# FMDET.net
KiCad netlist of a schematic drawn in Altium Designer
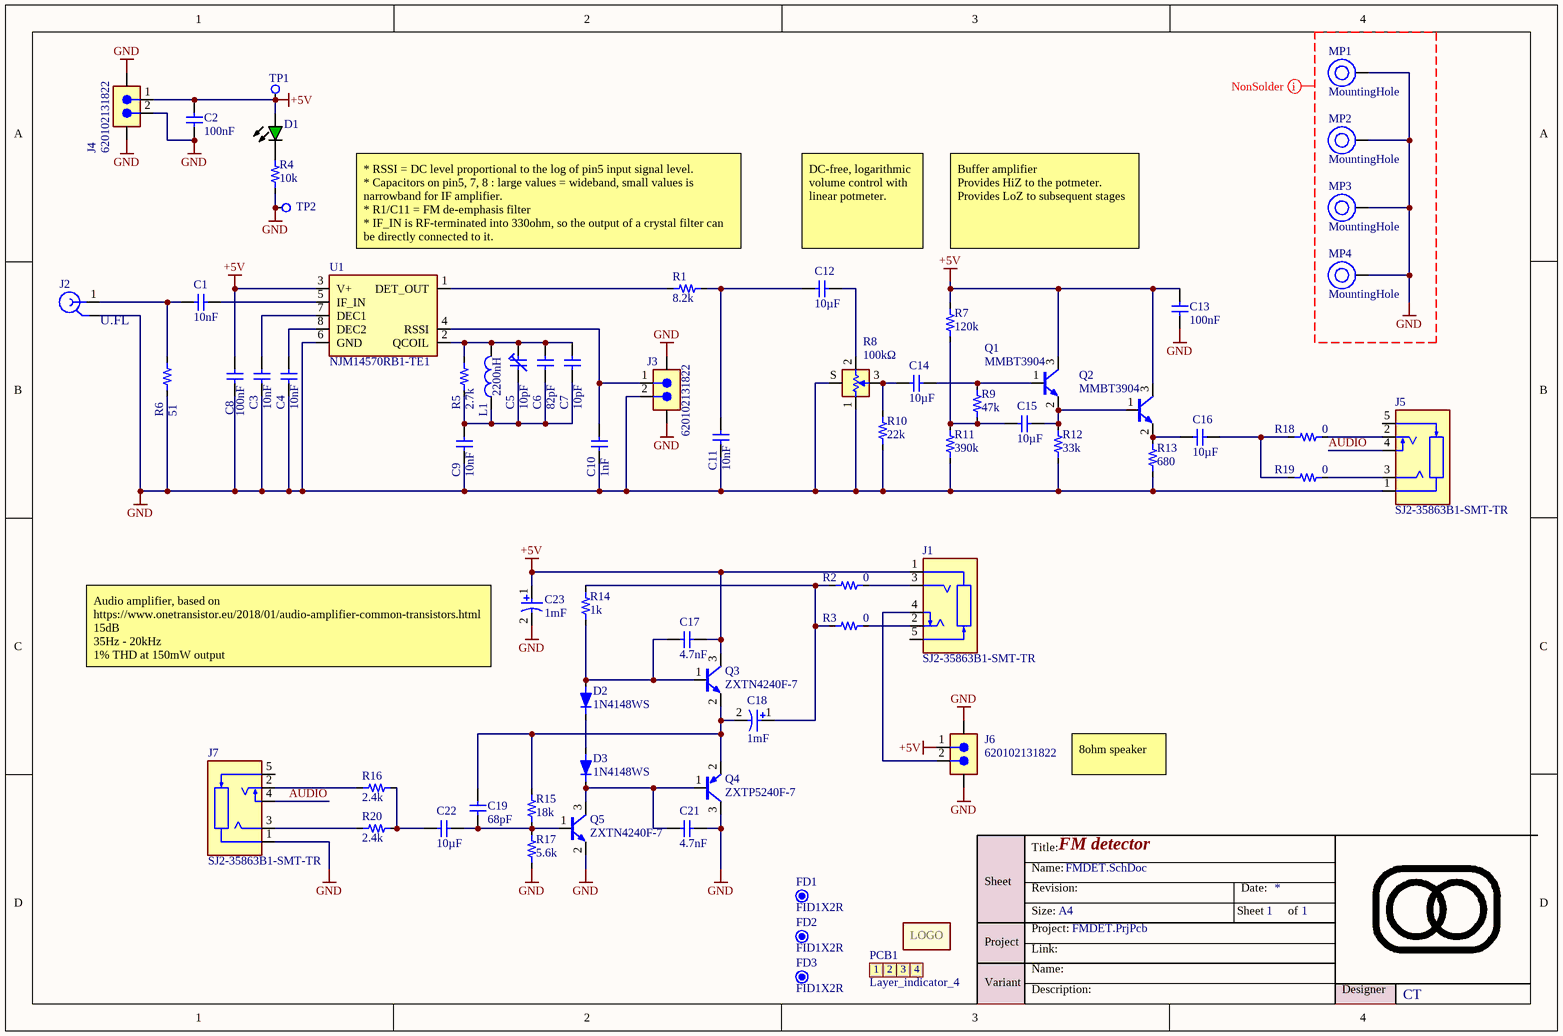
[diagram p0: FMDET.SchDoc]

(export (version "E")
  (design (tool "Eeschema 10.0.6"))
  (components
    (comp (ref "C1")
      (value "10nF")
      (footprint "0603-C-N")
      (description "Capacitor MLCC, General Purpose, size 0603, X7R, 10nF, +/-10%, 50V")
      (fields (field (name "TOLERANCE") "10%") (field (name "JLCPCB PART #") "C57112"))
      (libsource (lib "7c7 Engineering") (part "CAP-NP-2"))
    )
    (comp (ref "C2")
      (value "100nF")
      (footprint "0603-C-N")
      (description "Capacitor MLCC, General Purpose, size 0603, X7R, 100nF, +/-10%, 50V")
      (fields (field (name "TOLERANCE") "10%") (field (name "PAGE PART #") "CCQK104"))
      (libsource (lib "7c7 Engineering") (part "CAP-NP-2"))
    )
    (comp (ref "C3")
      (value "10nF")
      (footprint "0603-C-N")
      (description "Capacitor MLCC, General Purpose, size 0603, X7R, 10nF, +/-10%, 50V")
      (fields (field (name "TOLERANCE") "10%") (field (name "JLCPCB PART #") "C57112"))
      (libsource (lib "7c7 Engineering") (part "CAP-NP-2"))
    )
    (comp (ref "C4")
      (value "10nF")
      (footprint "0603-C-N")
      (description "Capacitor MLCC, General Purpose, size 0603, X7R, 10nF, +/-10%, 50V")
      (fields (field (name "TOLERANCE") "10%") (field (name "JLCPCB PART #") "C57112"))
      (libsource (lib "7c7 Engineering") (part "CAP-NP-2"))
    )
    (comp (ref "C5")
      (value "10pF")
      (footprint "SGC3S100-Footprint-1")
      (fields (field (name "JLCPCB PART #") "C22468121") (field (name "Comment") "SGC3S100"))
      (libsource (lib "7c7 Engineering") (part "CAP-TRIM"))
    )
    (comp (ref "C6")
      (value "82pF")
      (footprint "0603-C-N")
      (description "Multilayer Ceramic Chip Capacitor, General Purpose, size 0603, C0G, 82pF, 50VDC")
      (fields (field (name "TOLERANCE") "5%") (field (name "JLCPCB PART #") "C107056"))
      (libsource (lib "7c7 Engineering") (part "CAP-NP-2"))
    )
    (comp (ref "C7")
      (value "10pF")
      (footprint "0603-C-N")
      (description "WCAP-CSGP Multilayer Ceramic Chip Capacitor, General Purpose, size 0603, NP0, 10pF, 50VDC")
      (fields (field (name "JLCPCB PART #") "C106245") (field (name "TOLERANCE") "5%"))
      (libsource (lib "7c7 Engineering") (part "CAP-NP-2"))
    )
    (comp (ref "C8")
      (value "100nF")
      (footprint "0603-C-N")
      (description "Capacitor MLCC, General Purpose, size 0603, X7R, 100nF, +/-10%, 50V")
      (fields (field (name "TOLERANCE") "10%") (field (name "PAGE PART #") "CCQK104"))
      (libsource (lib "7c7 Engineering") (part "CAP-NP-2"))
    )
    (comp (ref "C9")
      (value "10nF")
      (footprint "0603-C-N")
      (description "Capacitor MLCC, General Purpose, size 0603, X7R, 10nF, +/-10%, 50V")
      (fields (field (name "TOLERANCE") "10%") (field (name "JLCPCB PART #") "C57112"))
      (libsource (lib "7c7 Engineering") (part "CAP-NP-2"))
    )
    (comp (ref "C10")
      (value "1nF")
      (footprint "0603-C-N")
      (description "WCAP-CSGP Multilayer Ceramic Chip Capacitor, General Purpose, size 0603, X7R, 1nF, 50VDC")
      (fields (field (name "TOLERANCE") "10%") (field (name "JLCPCB PART #") "C1588"))
      (libsource (lib "7c7 Engineering") (part "CAP-NP-2"))
    )
    (comp (ref "C11")
      (value "10nF")
      (footprint "0603-C-N")
      (description "Capacitor MLCC, General Purpose, size 0603, X7R, 10nF, +/-10%, 50V")
      (fields (field (name "TOLERANCE") "10%") (field (name "JLCPCB PART #") "C57112"))
      (libsource (lib "7c7 Engineering") (part "CAP-NP-2"))
    )
    (comp (ref "C12")
      (value "10µF")
      (footprint "WCAP-CSGP_1210_L3.2W2.5H2.5")
      (description "WCAP-CSGP Multilayer Ceramic Chip Capacitor, General Purpose, size 1210, X7R, 10µF, 50VDC")
      (fields (field (name "JLCPCB PART #") "C77102") (field (name "TOLERANCE") "10%"))
      (libsource (lib "7c7 Engineering") (part "CAP-NP-2"))
    )
    (comp (ref "C13")
      (value "100nF")
      (footprint "0603-C-N")
      (description "Capacitor MLCC, General Purpose, size 0603, X7R, 100nF, +/-10%, 50V")
      (fields (field (name "TOLERANCE") "10%") (field (name "PAGE PART #") "CCQK104"))
      (libsource (lib "7c7 Engineering") (part "CAP-NP-2"))
    )
    (comp (ref "C14")
      (value "10µF")
      (footprint "WCAP-CSGP_1210_L3.2W2.5H2.5")
      (description "WCAP-CSGP Multilayer Ceramic Chip Capacitor, General Purpose, size 1210, X7R, 10µF, 50VDC")
      (fields (field (name "JLCPCB PART #") "C77102") (field (name "TOLERANCE") "10%"))
      (libsource (lib "7c7 Engineering") (part "CAP-NP-2"))
    )
    (comp (ref "C15")
      (value "10µF")
      (footprint "WCAP-CSGP_1210_L3.2W2.5H2.5")
      (description "WCAP-CSGP Multilayer Ceramic Chip Capacitor, General Purpose, size 1210, X7R, 10µF, 50VDC")
      (fields (field (name "JLCPCB PART #") "C77102") (field (name "TOLERANCE") "10%"))
      (libsource (lib "7c7 Engineering") (part "CAP-NP-2"))
    )
    (comp (ref "C16")
      (value "10µF")
      (footprint "WCAP-CSGP_1210_L3.2W2.5H2.5")
      (description "WCAP-CSGP Multilayer Ceramic Chip Capacitor, General Purpose, size 1210, X7R, 10µF, 50VDC")
      (fields (field (name "JLCPCB PART #") "C77102") (field (name "TOLERANCE") "10%"))
      (libsource (lib "7c7 Engineering") (part "CAP-NP-2"))
    )
    (comp (ref "C17")
      (value "4.7nF")
      (footprint "0603-C-N")
      (description "Capacitor MLCC, General Purpose, size 0603, X7R, 4.7nF, +/-5%, 50V")
      (fields (field (name "TOLERANCE") "5%") (field (name "JLCPCB PART #") "C53987"))
      (libsource (lib "7c7 Engineering") (part "CAP-NP-2"))
    )
    (comp (ref "C18")
      (value "1mF")
      (footprint "WCAP-ATLI_D10H16")
      (description "Alum. Electrolytic Cap 1000F 10V 10MM Radial Wcap-atli; Lifetime 5000H +105°C")
      (fields (field (name "TOLERANCE") "20%") (field (name "JLCPCB PART #") "C43339"))
      (libsource (lib "7c7 Engineering") (part "CAP-P-2"))
    )
    (comp (ref "C19")
      (value "68pF")
      (footprint "0603-C-N")
      (description "Capacitor MLCC, General Purpose, size 0603, C0G, 68pF, +/-5%, 50V")
      (fields (field (name "JLCPCB PART #") "C62782") (field (name "TOLERANCE") "5%"))
      (libsource (lib "7c7 Engineering") (part "CAP-NP-2"))
    )
    (comp (ref "C21")
      (value "4.7nF")
      (footprint "0603-C-N")
      (description "Capacitor MLCC, General Purpose, size 0603, X7R, 4.7nF, +/-5%, 50V")
      (fields (field (name "TOLERANCE") "5%") (field (name "JLCPCB PART #") "C53987"))
      (libsource (lib "7c7 Engineering") (part "CAP-NP-2"))
    )
    (comp (ref "C22")
      (value "10µF")
      (footprint "WCAP-CSGP_1210_L3.2W2.5H2.5")
      (description "WCAP-CSGP Multilayer Ceramic Chip Capacitor, General Purpose, size 1210, X7R, 10µF, 50VDC")
      (fields (field (name "JLCPCB PART #") "C77102") (field (name "TOLERANCE") "10%"))
      (libsource (lib "7c7 Engineering") (part "CAP-NP-2"))
    )
    (comp (ref "C23")
      (value "1mF")
      (footprint "WCAP-ATLI_D10H16")
      (description "Alum. Electrolytic Cap 1000F 10V 10MM Radial Wcap-atli; Lifetime 5000H +105°C")
      (fields (field (name "TOLERANCE") "20%") (field (name "JLCPCB PART #") "C43339"))
      (libsource (lib "7c7 Engineering") (part "CAP-P-2"))
    )
    (comp (ref "D1")
      (value "150060GS84000")
      (footprint "WL-SMCW_0603_150060xx8x000")
      (description "WL-SMCW Mono-color Chip LED Waterclear, size 0603, Green, 3.3V, 40°")
      (fields (field (name "JLCPCB PART #") "C7429914") (field (name "MANUFACTURER") "Wurth Elektronik"))
      (libsource (lib "7c7 Engineering") (part "LED-GREEN-2"))
    )
    (comp (ref "D2")
      (value "1N4148WS")
      (footprint "SOD323-MFG")
      (description "Small Signal Diode, 75 V, 0.15 A, -55 to 150 degC, 2-Pin SOD-323, RoHS, Tape and Reel")
      (fields (field (name "JLCPCB BASIC PART") "Yes") (field (name "JLCPCB PART #") "C2128"))
      (libsource (lib "7c7 Engineering") (part "DIODE-2"))
    )
    (comp (ref "D3")
      (value "1N4148WS")
      (footprint "SOD323-MFG")
      (description "Small Signal Diode, 75 V, 0.15 A, -55 to 150 degC, 2-Pin SOD-323, RoHS, Tape and Reel")
      (fields (field (name "JLCPCB BASIC PART") "Yes") (field (name "JLCPCB PART #") "C2128"))
      (libsource (lib "7c7 Engineering") (part "DIODE-2"))
    )
    (comp (ref "FD1")
      (value "FID1X2R")
      (footprint "FID1X2R")
      (description "Fiducial - Round 1x2mm")
      (libsource (lib "7c7 Engineering") (part "CMP-00134-2"))
    )
    (comp (ref "FD2")
      (value "FID1X2R")
      (footprint "FID1X2R")
      (description "Fiducial - Round 1x2mm")
      (libsource (lib "7c7 Engineering") (part "CMP-00134-2"))
    )
    (comp (ref "FD3")
      (value "FID1X2R")
      (footprint "FID1X2R")
      (description "Fiducial - Round 1x2mm")
      (libsource (lib "7c7 Engineering") (part "CMP-00134-2"))
    )
    (comp (ref "J1")
      (value "SJ2-35863B1-SMT-TR")
      (footprint "SJ2-35863B1-SMT-TR-Footprint-1")
      (description "3.5 mm, Stereo, Right Angle, Surface Mount (SMT), Audio Jack Connector")
      (fields (field (name "JLCPCB PART #") "C381135"))
      (libsource (lib "7c7 Engineering") (part "CN_AUDIO_TRS_2SW"))
    )
    (comp (ref "J2")
      (value "U.FL-R-SMT(10)")
      (footprint "HRS-U.FL-R-SMT_V")
      (fields (field (name "JLCPCB PART #") "C88373") (field (name "MANUFACTURER") "Hirose Electric"))
      (libsource (lib "7c7 Engineering") (part "CN_COAX"))
    )
    (comp (ref "J3")
      (value "620102131822")
      (footprint "620102131822")
      (description "WR-WTB SMT Male Horizontal Shrouded Header, pitch 2mm, 2p")
      (fields
        (field (name "JLCPCB PART #") "C295747")
        (field (name "PAGE PART #") "K620102131822")
        (field (name "PUBLISHER") "Wurth Elektronik")
      )
      (libsource (lib "7c7 Engineering") (part "HDR_2P_2MP"))
    )
    (comp (ref "J4")
      (value "620102131822")
      (footprint "620102131822")
      (description "WR-WTB SMT Male Horizontal Shrouded Header, pitch 2mm, 2p")
      (fields
        (field (name "JLCPCB PART #") "C295747")
        (field (name "PAGE PART #") "K620102131822")
        (field (name "PUBLISHER") "Wurth Elektronik")
      )
      (libsource (lib "") (part "HDR_2P_2MP_1"))
    )
    (comp (ref "J5")
      (value "SJ2-35863B1-SMT-TR")
      (footprint "SJ2-35863B1-SMT-TR-Footprint-1")
      (description "3.5 mm, Stereo, Right Angle, Surface Mount (SMT), Audio Jack Connector")
      (fields (field (name "JLCPCB PART #") "C381135"))
      (libsource (lib "") (part "CN_AUDIO_TRS_2SW_2"))
    )
    (comp (ref "J6")
      (value "620102131822")
      (footprint "620102131822")
      (description "WR-WTB SMT Male Horizontal Shrouded Header, pitch 2mm, 2p")
      (fields
        (field (name "JLCPCB PART #") "C295747")
        (field (name "PAGE PART #") "K620102131822")
        (field (name "PUBLISHER") "Wurth Elektronik")
      )
      (libsource (lib "7c7 Engineering") (part "HDR_2P_2MP"))
    )
    (comp (ref "J7")
      (value "SJ2-35863B1-SMT-TR")
      (footprint "SJ2-35863B1-SMT-TR-Footprint-1")
      (description "3.5 mm, Stereo, Right Angle, Surface Mount (SMT), Audio Jack Connector")
      (fields (field (name "JLCPCB PART #") "C381135"))
      (libsource (lib "") (part "CN_AUDIO_TRS_2SW_1"))
    )
    (comp (ref "L1")
      (value "744762322A")
      (footprint "WE-RFI_1008")
      (description "WE-RFI Ferrite SMT Inductor, size 1008, 2200nH, 200mA, 160MHz")
      (fields
        (field (name "MANUFACTURER") "Wurth Elektronik")
        (field (name "INDUCTANCE") "2200nH")
        (field (name "JLCPCB PART #") "C703712")
      )
      (libsource (lib "7c7 Engineering") (part "IND"))
    )
    (comp (ref "M1")
      (value "Logo")
      (footprint "LOGO_9x6mm")
      (libsource (lib "Integrated_Library_LieBtrau") (part "Logo"))
    )
    (comp (ref "MP1")
      (value "MountingHole")
      (footprint "PTH-M3D6.5_VIA-RING")
      (libsource (lib "7c7 Engineering") (part "MECH_NO_BOM"))
    )
    (comp (ref "MP2")
      (value "MountingHole")
      (footprint "PTH-M3D6.5_VIA-RING")
      (libsource (lib "7c7 Engineering") (part "MECH_NO_BOM"))
    )
    (comp (ref "MP3")
      (value "MountingHole")
      (footprint "PTH-M3D6.5_VIA-RING")
      (libsource (lib "7c7 Engineering") (part "MECH_NO_BOM"))
    )
    (comp (ref "MP4")
      (value "MountingHole")
      (footprint "PTH-M3D6.5_VIA-RING")
      (libsource (lib "7c7 Engineering") (part "MECH_NO_BOM"))
    )
    (comp (ref "PCB1")
      (value "Layer_indicator_4")
      (footprint "LayerId_4L_4x1.5mm")
      (description "Layer indicator for 4 layers")
      (libsource (lib "7c7 Engineering") (part "Layer_indicator_4-Symbol-1"))
    )
    (comp (ref "Q1")
      (value "MMBT3904")
      (footprint "SOT-23-3-N")
      (description "NPN General Purpose Amplifier, 40 V, 0.2 A, -55 to 150 degC, 3-Pin SOT23, RoHS, Tape and Reel")
      (fields (field (name "JLCPCB PART #") "C20526") (field (name "MANUFACTURER") "Fairchild Semiconductor"))
      (libsource (lib "7c7 Engineering") (part "BJT-NPN-BEC"))
    )
    (comp (ref "Q2")
      (value "MMBT3904")
      (footprint "SOT-23-3-N")
      (description "NPN General Purpose Amplifier, 40 V, 0.2 A, -55 to 150 degC, 3-Pin SOT23, RoHS, Tape and Reel")
      (fields (field (name "JLCPCB PART #") "C20526") (field (name "MANUFACTURER") "Fairchild Semiconductor"))
      (libsource (lib "7c7 Engineering") (part "BJT-NPN-BEC"))
    )
    (comp (ref "Q3")
      (value "ZXTN4240F-7")
      (footprint "SOT-23-3-N")
      (description "Trans GP BJT NPN 40V 2A 730mW Automotive 3-Pin SOT-23 T/R")
      (fields (field (name "JLCPCB BASIC PART") "No") (field (name "JLCPCB PART #") "C513079"))
      (libsource (lib "7c7 Engineering") (part "BJT-NPN-BEC"))
    )
    (comp (ref "Q4")
      (value "ZXTP5240F-7")
      (footprint "SOT-23-3-N")
      (description "Bipolar Transistors - BJT 40V PNP SS Mid-Perf Transistor")
      (fields (field (name "JLCPCB BASIC PART") "No") (field (name "JLCPCB PART #") "C3199979"))
      (libsource (lib "7c7 Engineering") (part "BJT-PNP-BEC"))
    )
    (comp (ref "Q5")
      (value "ZXTN4240F-7")
      (footprint "SOT-23-3-N")
      (description "Trans GP BJT NPN 40V 2A 730mW Automotive 3-Pin SOT-23 T/R")
      (fields (field (name "JLCPCB PART #") "C513079") (field (name "JLCPCB BASIC PART") "No"))
      (libsource (lib "7c7 Engineering") (part "BJT-NPN-BEC"))
    )
    (comp (ref "R1")
      (value "8.2k")
      (footprint "0603-R-N")
      (description "Res Thick Film 0603 8.2K Ohm 1% 0.1W(1/10W) ±100ppm/C Pad SMD T/R")
      (fields (field (name "TOLERANCE") "1%") (field (name "JLCPCB PART #") "C25981"))
      (libsource (lib "7c7 Engineering") (part "RES"))
    )
    (comp (ref "R2")
      (value "0")
      (footprint "0603-R-N")
      (description "Chip Jumper, Thick Film, Jumper, 0603, 100mW, 1A, 0 Ohm, <50 mOhm")
      (fields (field (name "FLIR PART #") "YRES0E-1") (field (name "PAGE PART #") "ROQJ0000"))
      (libsource (lib "7c7 Engineering") (part "RES"))
    )
    (comp (ref "R3")
      (value "0")
      (footprint "0603-R-N")
      (description "Chip Jumper, Thick Film, Jumper, 0603, 100mW, 1A, 0 Ohm, <50 mOhm")
      (fields (field (name "FLIR PART #") "YRES0E-1") (field (name "PAGE PART #") "ROQJ0000"))
      (libsource (lib "7c7 Engineering") (part "RES"))
    )
    (comp (ref "R4")
      (value "10k")
      (footprint "0603-R-N")
      (description "Chip Resistor, Thick Film, General Purpose, 0603, 100mW, 50V, 10 kOhm, +/-1%")
      (fields (field (name "FLIR PART #") "YRES10K-1") (field (name "PAGE PART #") "ROQF1002"))
      (libsource (lib "7c7 Engineering") (part "RES"))
    )
    (comp (ref "R5")
      (value "2.7k")
      (footprint "0603-R-N")
      (description "Res Thick Film 0603 2.7K Ohm 1% 0.1W(1/10W) ±100ppm/C Pad SMD Automotive T/R")
      (fields (field (name "TOLERANCE") "1%") (field (name "JLCPCB PART #") "C13167"))
      (libsource (lib "7c7 Engineering") (part "RES"))
    )
    (comp (ref "R6")
      (value "51")
      (footprint "0603-R-N")
      (description "Res Thick Film 0603 51 Ohm 1% 1/10W ±100ppm/°C Molded SMD SMD Paper T/R")
      (fields (field (name "JLCPCB PART #") "C23197") (field (name "TOLERANCE") "1%"))
      (libsource (lib "7c7 Engineering") (part "RES"))
    )
    (comp (ref "R7")
      (value "120k")
      (footprint "0603-R-N")
      (description "Res Thick Film 0603 120K Ohm 1% 0.1W(1/10W) ±100ppm/°C Pad SMD T/R")
      (fields (field (name "TOLERANCE") "1%") (field (name "JLCPCB PART #") "C25808"))
      (libsource (lib "7c7 Engineering") (part "RES"))
    )
    (comp (ref "R8")
      (value "100kΩ")
      (footprint "PTV09A-4020F-B104-Footprint-1")
      (description "Potentiometer, Carbon, 0.05W, 100000ohm, 20V, 20% +/-Tol, 1 Turn(s)")
      (fields (field (name "JLCPCB PART #") "C5154557") (field (name "TOLERANCE") "20%"))
      (libsource (lib "7c7 Engineering") (part "RES-ADJ-3_SHIELD"))
    )
    (comp (ref "R9")
      (value "47k")
      (footprint "0603-R-N")
      (description "Chip Resistor, Thick Film, General Purpose, 0603, 100mW, 50V, 47 kOhm, +/-1%")
      (fields (field (name "FLIR PART #") "YRES47K-1") (field (name "PAGE PART #") "ROQF4702"))
      (libsource (lib "7c7 Engineering") (part "RES"))
    )
    (comp (ref "R10")
      (value "22k")
      (footprint "0603-R-N")
      (description "Chip Resistor, Thick Film, General Purpose, 0603, 100mW, 50V, 22 kOhm, +/-1%")
      (fields (field (name "JLCPCB PART #") "C31850") (field (name "TOLERANCE") "1%"))
      (libsource (lib "7c7 Engineering") (part "RES"))
    )
    (comp (ref "R11")
      (value "390k")
      (footprint "0603-R-N")
      (description "SMD Chip Resistor, 390 kOhm, ± 1%, 100 mW, 0603 [1608 Metric], Thick Film, General Purpose")
      (fields (field (name "JLCPCB PART #") "C23150") (field (name "TOLERANCE") "1%"))
      (libsource (lib "7c7 Engineering") (part "RES"))
    )
    (comp (ref "R12")
      (value "33k")
      (footprint "0603-R-N")
      (description "Chip Resistor, Thick Film, General Purpose, 0603, 100mW, 50V, 33 kOhm, +/-1%")
      (fields (field (name "TOLERANCE") "1%") (field (name "JLCPCB PART #") "C4216"))
      (libsource (lib "7c7 Engineering") (part "RES"))
    )
    (comp (ref "R13")
      (value "680")
      (footprint "0603-R-N")
      (description "SMD Chip Resistor, 680 Ohm, ï¿½ 1%, 100 mW, 0603 [1608 Metric], Thick Film, Precision")
      (fields (field (name "JLCPCB PART #") "C23228") (field (name "TOLERANCE") "1%"))
      (libsource (lib "7c7 Engineering") (part "RES"))
    )
    (comp (ref "R14")
      (value "1k")
      (footprint "0603-R-N")
      (description "Chip Resistor, Thick Film, General Purpose, 0603, 100mW, 50V, 1 kOhm, +/-1%")
      (fields (field (name "JLCPCB BASIC PART") "Yes") (field (name "TOLERANCE") "1%"))
      (libsource (lib "7c7 Engineering") (part "RES"))
    )
    (comp (ref "R15")
      (value "18k")
      (footprint "0603-R-N")
      (description "Chip Resistor, Thick Film, General Purpose, 0603, 100mW, 50V, 18 kOhm, +/-1%")
      (fields (field (name "TOLERANCE") "1%") (field (name "PAGE PART #") "ROQF1802"))
      (libsource (lib "7c7 Engineering") (part "RES"))
    )
    (comp (ref "R16")
      (value "2.4k")
      (footprint "0603-R-N")
      (description "Chip Resistor, Thick Film, General Purpose, 0603, 100mW, 50V, 2.4 kOhm, +/-1%")
      (fields (field (name "JLCPCB PART #") "C22940") (field (name "TOLERANCE") "1%"))
      (libsource (lib "7c7 Engineering") (part "RES"))
    )
    (comp (ref "R17")
      (value "5.6k")
      (footprint "0603-R-N")
      (description "Res Thick Film 0603 5.6K Ohm 1% 0.1W(1/10W) ±100ppm/C Pad SMD T/R")
      (fields (field (name "TOLERANCE") "1%") (field (name "JLCPCB PART #") "C23189"))
      (libsource (lib "7c7 Engineering") (part "RES"))
    )
    (comp (ref "R18")
      (value "0")
      (footprint "0603-R-N")
      (description "Chip Jumper, Thick Film, Jumper, 0603, 100mW, 1A, 0 Ohm, <50 mOhm")
      (fields (field (name "FLIR PART #") "YRES0E-1") (field (name "PAGE PART #") "ROQJ0000"))
      (libsource (lib "7c7 Engineering") (part "RES"))
    )
    (comp (ref "R19")
      (value "0")
      (footprint "0603-R-N")
      (description "Chip Jumper, Thick Film, Jumper, 0603, 100mW, 1A, 0 Ohm, <50 mOhm")
      (fields (field (name "FLIR PART #") "YRES0E-1") (field (name "PAGE PART #") "ROQJ0000"))
      (libsource (lib "7c7 Engineering") (part "RES"))
    )
    (comp (ref "R20")
      (value "2.4k")
      (footprint "0603-R-N")
      (description "Chip Resistor, Thick Film, General Purpose, 0603, 100mW, 50V, 2.4 kOhm, +/-1%")
      (fields (field (name "JLCPCB PART #") "C22940") (field (name "TOLERANCE") "1%"))
      (libsource (lib "7c7 Engineering") (part "RES"))
    )
    (comp (ref "TP1")
      (value "Testpad with multiple sizes")
      (footprint "TP_1.5mm_0.3mmHole")
      (description "Testpad land")
      (libsource (lib "7c7 Engineering") (part "Testpad"))
    )
    (comp (ref "TP2")
      (value "Testpad with multiple sizes")
      (footprint "TP_1.5mm_0.3mmHole")
      (description "Testpad land")
      (libsource (lib "7c7 Engineering") (part "Testpad"))
    )
    (comp (ref "U1")
      (value "NJM14570RB1-TE1")
      (footprint "MSOP8")
      (description "Modulator / Demodulator Wide-B FM IF Demod 1.8 to 9V 2.9mA 15")
      (fields (field (name "JLCPCB PART #") "C5200653"))
      (libsource (lib "7c7 Engineering") (part "NJM14570RB1-TE1-Symbol-1"))
    )
  )
  (nets
    (net (code "1") (name "+5V") (class "Default")
      (node (ref "C13") (pin "2") (pinfunction "2_2") (pintype "passive"))
      (node (ref "C17") (pin "2") (pinfunction "2_2") (pintype "passive"))
      (node (ref "C2") (pin "2") (pinfunction "2_2") (pintype "passive"))
      (node (ref "C23") (pin "1") (pinfunction "1_1") (pintype "passive"))
      (node (ref "C8") (pin "2") (pinfunction "2_2") (pintype "passive"))
      (node (ref "D1") (pin "2") (pinfunction "A_2") (pintype "passive"))
      (node (ref "J1") (pin "1") (pinfunction "1_1") (pintype "passive"))
      (node (ref "J4") (pin "1") (pinfunction "1_1") (pintype "passive"))
      (node (ref "J6") (pin "1") (pinfunction "1_1") (pintype "passive"))
      (node (ref "Q1") (pin "3") (pinfunction "C_3") (pintype "passive"))
      (node (ref "Q2") (pin "3") (pinfunction "C_3") (pintype "passive"))
      (node (ref "Q3") (pin "3") (pinfunction "C_3") (pintype "passive"))
      (node (ref "R7") (pin "2") (pinfunction "2_2") (pintype "passive"))
      (node (ref "TP1") (pin "1") (pinfunction "Pad_1") (pintype "passive"))
      (node (ref "U1") (pin "3") (pinfunction "V+_3") (pintype "power_in"))
    )
    (net (code "2") (name "/AUDIO") (class "Default")
      (node (ref "J5") (pin "4") (pinfunction "4_4") (pintype "passive"))
      (node (ref "J7") (pin "4") (pinfunction "4_4") (pintype "passive"))
    )
    (net (code "3") (name "GND") (class "Default")
      (node (ref "C10") (pin "1") (pinfunction "1_1") (pintype "passive"))
      (node (ref "C11") (pin "1") (pinfunction "1_1") (pintype "passive"))
      (node (ref "C13") (pin "1") (pinfunction "1_1") (pintype "passive"))
      (node (ref "C2") (pin "1") (pinfunction "1_1") (pintype "passive"))
      (node (ref "C21") (pin "2") (pinfunction "2_2") (pintype "passive"))
      (node (ref "C23") (pin "2") (pinfunction "2_2") (pintype "passive"))
      (node (ref "C3") (pin "1") (pinfunction "1_1") (pintype "passive"))
      (node (ref "C4") (pin "1") (pinfunction "1_1") (pintype "passive"))
      (node (ref "C8") (pin "1") (pinfunction "1_1") (pintype "passive"))
      (node (ref "C9") (pin "1") (pinfunction "1_1") (pintype "passive"))
      (node (ref "J2") (pin "2") (pinfunction "GND_2") (pintype "passive"))
      (node (ref "J3") (pin "2") (pinfunction "2_2") (pintype "passive"))
      (node (ref "J3") (pin "MP1") (pinfunction "MP1_MP1") (pintype "passive"))
      (node (ref "J3") (pin "MP2") (pinfunction "MP2_MP2") (pintype "passive"))
      (node (ref "J4") (pin "2") (pinfunction "2_2") (pintype "passive"))
      (node (ref "J4") (pin "MP1") (pinfunction "MP1_MP1") (pintype "passive"))
      (node (ref "J4") (pin "MP2") (pinfunction "MP2_MP2") (pintype "passive"))
      (node (ref "J5") (pin "1") (pinfunction "1_1") (pintype "passive"))
      (node (ref "J6") (pin "MP1") (pinfunction "MP1_MP1") (pintype "passive"))
      (node (ref "J6") (pin "MP2") (pinfunction "MP2_MP2") (pintype "passive"))
      (node (ref "J7") (pin "1") (pinfunction "1_1") (pintype "passive"))
      (node (ref "MP1") (pin "1") (pinfunction "H1_1") (pintype "passive"))
      (node (ref "MP2") (pin "1") (pinfunction "H1_1") (pintype "passive"))
      (node (ref "MP3") (pin "1") (pinfunction "H1_1") (pintype "passive"))
      (node (ref "MP4") (pin "1") (pinfunction "H1_1") (pintype "passive"))
      (node (ref "Q4") (pin "3") (pinfunction "C_3") (pintype "passive"))
      (node (ref "Q5") (pin "2") (pinfunction "E_2") (pintype "passive"))
      (node (ref "R10") (pin "1") (pinfunction "1_1") (pintype "passive"))
      (node (ref "R11") (pin "1") (pinfunction "1_1") (pintype "passive"))
      (node (ref "R12") (pin "1") (pinfunction "1_1") (pintype "passive"))
      (node (ref "R13") (pin "1") (pinfunction "1_1") (pintype "passive"))
      (node (ref "R17") (pin "1") (pinfunction "1_1") (pintype "passive"))
      (node (ref "R4") (pin "1") (pinfunction "1_1") (pintype "passive"))
      (node (ref "R6") (pin "1") (pinfunction "1_1") (pintype "passive"))
      (node (ref "R8") (pin "1") (pinfunction "A_1") (pintype "passive"))
      (node (ref "R8") (pin "S") (pinfunction "S_S") (pintype "passive"))
      (node (ref "TP2") (pin "1") (pinfunction "Pad_1") (pintype "passive"))
      (node (ref "U1") (pin "6") (pinfunction "GND_6") (pintype "passive"))
    )
    (net (code "4") (name "Net-(C5-Pad1)") (class "Default")
      (node (ref "C5") (pin "1") (pinfunction "1_1") (pintype "passive"))
      (node (ref "C6") (pin "1") (pinfunction "1_1") (pintype "passive"))
      (node (ref "C7") (pin "1") (pinfunction "1_1") (pintype "passive"))
      (node (ref "C9") (pin "2") (pinfunction "2_2") (pintype "passive"))
      (node (ref "L1") (pin "1") (pinfunction "1_1") (pintype "passive"))
      (node (ref "R5") (pin "1") (pinfunction "1_1") (pintype "passive"))
    )
    (net (code "5") (name "Net-(C11-Pad2)") (class "Default")
      (node (ref "C11") (pin "2") (pinfunction "2_2") (pintype "passive"))
      (node (ref "C12") (pin "1") (pinfunction "1_1") (pintype "passive"))
      (node (ref "R1") (pin "1") (pinfunction "1_1") (pintype "passive"))
    )
    (net (code "6") (name "Net-(C15-Pad1)") (class "Default")
      (node (ref "C15") (pin "1") (pinfunction "1_1") (pintype "passive"))
      (node (ref "R11") (pin "2") (pinfunction "2_2") (pintype "passive"))
      (node (ref "R7") (pin "1") (pinfunction "1_1") (pintype "passive"))
      (node (ref "R9") (pin "2") (pinfunction "2_2") (pintype "passive"))
    )
    (net (code "7") (name "Net-(C16-Pad2)") (class "Default")
      (node (ref "C16") (pin "2") (pinfunction "2_2") (pintype "passive"))
      (node (ref "R18") (pin "2") (pinfunction "2_2") (pintype "passive"))
      (node (ref "R19") (pin "2") (pinfunction "2_2") (pintype "passive"))
    )
    (net (code "8") (name "Net-(C18-Pad1)") (class "Default")
      (node (ref "C18") (pin "1") (pinfunction "1_1") (pintype "passive"))
      (node (ref "R14") (pin "1") (pinfunction "1_1") (pintype "passive"))
      (node (ref "R2") (pin "1") (pinfunction "1_1") (pintype "passive"))
      (node (ref "R3") (pin "1") (pinfunction "1_1") (pintype "passive"))
    )
    (net (code "9") (name "Net-(C22-Pad2)") (class "Default")
      (node (ref "C22") (pin "2") (pinfunction "2_2") (pintype "passive"))
      (node (ref "R16") (pin "2") (pinfunction "2_2") (pintype "passive"))
      (node (ref "R20") (pin "2") (pinfunction "2_2") (pintype "passive"))
    )
    (net (code "10") (name "Net-(D1-K)") (class "Default")
      (node (ref "D1") (pin "1") (pinfunction "K_1") (pintype "passive"))
      (node (ref "R4") (pin "2") (pinfunction "2_2") (pintype "passive"))
    )
    (net (code "11") (name "Net-(D2-A)") (class "Default")
      (node (ref "C17") (pin "1") (pinfunction "1_1") (pintype "passive"))
      (node (ref "D2") (pin "2") (pinfunction "A_2") (pintype "passive"))
      (node (ref "Q3") (pin "1") (pinfunction "B_1") (pintype "passive"))
      (node (ref "R14") (pin "2") (pinfunction "2_2") (pintype "passive"))
    )
    (net (code "12") (name "Net-(D2-K)") (class "Default")
      (node (ref "D2") (pin "1") (pinfunction "K_1") (pintype "passive"))
      (node (ref "D3") (pin "2") (pinfunction "A_2") (pintype "passive"))
    )
    (net (code "13") (name "Net-(D3-K)") (class "Default")
      (node (ref "C21") (pin "1") (pinfunction "1_1") (pintype "passive"))
      (node (ref "D3") (pin "1") (pinfunction "K_1") (pintype "passive"))
      (node (ref "Q4") (pin "1") (pinfunction "B_1") (pintype "passive"))
      (node (ref "Q5") (pin "3") (pinfunction "C_3") (pintype "passive"))
    )
    (net (code "14") (name "Net-(J1-Pad2)") (class "Default")
      (node (ref "J1") (pin "2") (pinfunction "2_2") (pintype "passive"))
      (node (ref "R3") (pin "2") (pinfunction "2_2") (pintype "passive"))
    )
    (net (code "15") (name "Net-(J1-Pad3)") (class "Default")
      (node (ref "J1") (pin "3") (pinfunction "3_3") (pintype "passive"))
      (node (ref "R2") (pin "2") (pinfunction "2_2") (pintype "passive"))
    )
    (net (code "16") (name "Net-(J1-Pad4)") (class "Default")
      (node (ref "J1") (pin "4") (pinfunction "4_4") (pintype "passive"))
      (node (ref "J6") (pin "2") (pinfunction "2_2") (pintype "passive"))
    )
    (net (code "17") (name "Net-(J2-SIG)") (class "Default")
      (node (ref "C1") (pin "2") (pinfunction "2_2") (pintype "passive"))
      (node (ref "J2") (pin "1") (pinfunction "SIG_1") (pintype "passive"))
      (node (ref "R6") (pin "2") (pinfunction "2_2") (pintype "passive"))
    )
    (net (code "18") (name "Net-(J5-Pad2)") (class "Default")
      (node (ref "J5") (pin "2") (pinfunction "2_2") (pintype "passive"))
      (node (ref "R18") (pin "1") (pinfunction "1_1") (pintype "passive"))
    )
    (net (code "19") (name "Net-(J5-Pad3)") (class "Default")
      (node (ref "J5") (pin "3") (pinfunction "3_3") (pintype "passive"))
      (node (ref "R19") (pin "1") (pinfunction "1_1") (pintype "passive"))
    )
    (net (code "20") (name "Net-(J7-Pad2)") (class "Default")
      (node (ref "J7") (pin "2") (pinfunction "2_2") (pintype "passive"))
      (node (ref "R16") (pin "1") (pinfunction "1_1") (pintype "passive"))
    )
    (net (code "21") (name "Net-(J7-Pad3)") (class "Default")
      (node (ref "J7") (pin "3") (pinfunction "3_3") (pintype "passive"))
      (node (ref "R20") (pin "1") (pinfunction "1_1") (pintype "passive"))
    )
    (net (code "22") (name "Net-(Q1-B)") (class "Default")
      (node (ref "C14") (pin "2") (pinfunction "2_2") (pintype "passive"))
      (node (ref "Q1") (pin "1") (pinfunction "B_1") (pintype "passive"))
      (node (ref "R9") (pin "1") (pinfunction "1_1") (pintype "passive"))
    )
    (net (code "23") (name "Net-(Q1-E)") (class "Default")
      (node (ref "C15") (pin "2") (pinfunction "2_2") (pintype "passive"))
      (node (ref "Q1") (pin "2") (pinfunction "E_2") (pintype "passive"))
      (node (ref "Q2") (pin "1") (pinfunction "B_1") (pintype "passive"))
      (node (ref "R12") (pin "2") (pinfunction "2_2") (pintype "passive"))
    )
    (net (code "24") (name "Net-(Q2-E)") (class "Default")
      (node (ref "C16") (pin "1") (pinfunction "1_1") (pintype "passive"))
      (node (ref "Q2") (pin "2") (pinfunction "E_2") (pintype "passive"))
      (node (ref "R13") (pin "2") (pinfunction "2_2") (pintype "passive"))
    )
    (net (code "25") (name "Net-(Q3-E)") (class "Default")
      (node (ref "C18") (pin "2") (pinfunction "2_2") (pintype "passive"))
      (node (ref "C19") (pin "2") (pinfunction "2_2") (pintype "passive"))
      (node (ref "Q3") (pin "2") (pinfunction "E_2") (pintype "passive"))
      (node (ref "Q4") (pin "2") (pinfunction "E_2") (pintype "passive"))
      (node (ref "R15") (pin "2") (pinfunction "2_2") (pintype "passive"))
    )
    (net (code "26") (name "Net-(Q5-B)") (class "Default")
      (node (ref "C19") (pin "1") (pinfunction "1_1") (pintype "passive"))
      (node (ref "C22") (pin "1") (pinfunction "1_1") (pintype "passive"))
      (node (ref "Q5") (pin "1") (pinfunction "B_1") (pintype "passive"))
      (node (ref "R15") (pin "1") (pinfunction "1_1") (pintype "passive"))
      (node (ref "R17") (pin "2") (pinfunction "2_2") (pintype "passive"))
    )
    (net (code "27") (name "Net-(R8-B)") (class "Default")
      (node (ref "C12") (pin "2") (pinfunction "2_2") (pintype "passive"))
      (node (ref "R8") (pin "2") (pinfunction "B_2") (pintype "passive"))
    )
    (net (code "28") (name "Net-(R8-TAP)") (class "Default")
      (node (ref "C14") (pin "1") (pinfunction "1_1") (pintype "passive"))
      (node (ref "R10") (pin "2") (pinfunction "2_2") (pintype "passive"))
      (node (ref "R8") (pin "3") (pinfunction "TAP_3") (pintype "passive"))
    )
    (net (code "29") (name "Net-(U1-DEC1)") (class "Default")
      (node (ref "C3") (pin "2") (pinfunction "2_2") (pintype "passive"))
      (node (ref "U1") (pin "7") (pinfunction "DEC1_7") (pintype "passive"))
    )
    (net (code "30") (name "Net-(U1-DEC2)") (class "Default")
      (node (ref "C4") (pin "2") (pinfunction "2_2") (pintype "passive"))
      (node (ref "U1") (pin "8") (pinfunction "DEC2_8") (pintype "passive"))
    )
    (net (code "31") (name "Net-(U1-DET_OUT)") (class "Default")
      (node (ref "R1") (pin "2") (pinfunction "2_2") (pintype "passive"))
      (node (ref "U1") (pin "1") (pinfunction "DET_OUT_1") (pintype "passive"))
    )
    (net (code "32") (name "Net-(U1-IF_IN)") (class "Default")
      (node (ref "C1") (pin "1") (pinfunction "1_1") (pintype "passive"))
      (node (ref "U1") (pin "5") (pinfunction "IF_IN_5") (pintype "passive"))
    )
    (net (code "33") (name "Net-(U1-QCOIL)") (class "Default")
      (node (ref "C5") (pin "2") (pinfunction "2_2") (pintype "passive"))
      (node (ref "C6") (pin "2") (pinfunction "2_2") (pintype "passive"))
      (node (ref "C7") (pin "2") (pinfunction "2_2") (pintype "passive"))
      (node (ref "L1") (pin "2") (pinfunction "2_2") (pintype "passive"))
      (node (ref "R5") (pin "2") (pinfunction "2_2") (pintype "passive"))
      (node (ref "U1") (pin "2") (pinfunction "QCOIL_2") (pintype "passive"))
    )
    (net (code "34") (name "Net-(U1-RSSI)") (class "Default")
      (node (ref "C10") (pin "2") (pinfunction "2_2") (pintype "passive"))
      (node (ref "J3") (pin "1") (pinfunction "1_1") (pintype "passive"))
      (node (ref "U1") (pin "4") (pinfunction "RSSI_4") (pintype "passive"))
    )
    (net (code "35") (name "unconnected-(J1-Pad5)") (class "Default")
      (node (ref "J1") (pin "5") (pinfunction "5_5") (pintype "passive"))
    )
    (net (code "36") (name "unconnected-(J5-Pad5)") (class "Default")
      (node (ref "J5") (pin "5") (pinfunction "5_5") (pintype "passive"))
    )
    (net (code "37") (name "unconnected-(J7-Pad5)") (class "Default")
      (node (ref "J7") (pin "5") (pinfunction "5_5") (pintype "passive"))
    )
  )
)
